# busfahrer_pi.net
KiCad netlist of a schematic drawn in EAGLE
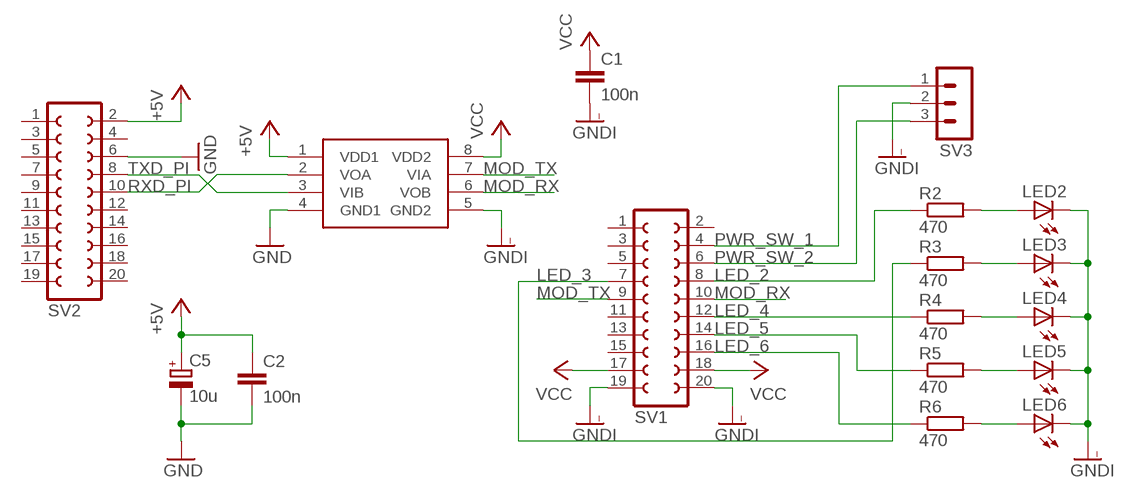
[diagram p0: schematic, sheet 1]

(export (version "E")
  (design (tool "Eeschema 10.0.6"))
  (components
    (comp (ref "C1")
      (value "100n")
      (footprint "eagle-import:C0805")
      (libsource (lib "eagle-import") (part "C-EUC0805"))
    )
    (comp (ref "C2")
      (value "100n")
      (footprint "eagle-import:C0805")
      (libsource (lib "eagle-import") (part "C-EUC0805"))
    )
    (comp (ref "C5")
      (value "10u")
      (footprint "eagle-import:E1,8-4")
      (libsource (lib "eagle-import") (part "CPOL-EUE1.8-4"))
    )
    (comp (ref "LED2")
      (value "LEDCHIPLED_0805")
      (footprint "eagle-import:CHIPLED_0805")
      (libsource (lib "eagle-import") (part "LEDCHIPLED_0805"))
    )
    (comp (ref "LED3")
      (value "LEDCHIPLED_0805")
      (footprint "eagle-import:CHIPLED_0805")
      (libsource (lib "eagle-import") (part "LEDCHIPLED_0805"))
    )
    (comp (ref "LED4")
      (value "LEDCHIPLED_0805")
      (footprint "eagle-import:CHIPLED_0805")
      (libsource (lib "eagle-import") (part "LEDCHIPLED_0805"))
    )
    (comp (ref "LED5")
      (value "LEDCHIPLED_0805")
      (footprint "eagle-import:CHIPLED_0805")
      (libsource (lib "eagle-import") (part "LEDCHIPLED_0805"))
    )
    (comp (ref "LED6")
      (value "LEDCHIPLED_0805")
      (footprint "eagle-import:CHIPLED_0805")
      (libsource (lib "eagle-import") (part "LEDCHIPLED_0805"))
    )
    (comp (ref "R2")
      (value "470")
      (footprint "eagle-import:R0805")
      (libsource (lib "eagle-import") (part "R-EU_R0805"))
    )
    (comp (ref "R3")
      (value "470")
      (footprint "eagle-import:R0805")
      (libsource (lib "eagle-import") (part "R-EU_R0805"))
    )
    (comp (ref "R4")
      (value "470")
      (footprint "eagle-import:R0805")
      (libsource (lib "eagle-import") (part "R-EU_R0805"))
    )
    (comp (ref "R5")
      (value "470")
      (footprint "eagle-import:R0805")
      (libsource (lib "eagle-import") (part "R-EU_R0805"))
    )
    (comp (ref "R6")
      (value "470")
      (footprint "eagle-import:R0805")
      (libsource (lib "eagle-import") (part "R-EU_R0805"))
    )
    (comp (ref "SV1")
      (value "FE10-2")
      (footprint "eagle-import:FE10-2")
      (libsource (lib "eagle-import") (part "FE10-2"))
    )
    (comp (ref "SV2")
      (value "FE10-2")
      (footprint "eagle-import:FE10-2")
      (fields (field (name "OC_FARNELL") "unknown") (field (name "OC_NEWARK") "unknown"))
      (libsource (lib "eagle-import") (part "FE10-2"))
    )
    (comp (ref "SV3")
      (value "MA03-1")
      (footprint "eagle-import:MA03-1")
      (libsource (lib "eagle-import") (part "MA03-1"))
    )
    (comp (ref "U$1")
      (value "ADUM3211")
      (footprint "eagle-import:SO8")
      (libsource (lib "eagle-import") (part "ADUM3211"))
    )
  )
  (nets
    (net (code "1") (name "+5V") (class "Default")
      (node (ref "C2") (pin "1") (pinfunction "1_1") (pintype "passive"))
      (node (ref "C5") (pin "+") (pinfunction "+_+") (pintype "passive"))
      (node (ref "SV2") (pin "2") (pinfunction "2_2") (pintype "passive"))
      (node (ref "U$1") (pin "1") (pinfunction "VDD1_1") (pintype "bidirectional"))
    )
    (net (code "2") (name "/LED_2") (class "Default")
      (node (ref "R2") (pin "1") (pinfunction "1_1") (pintype "passive"))
      (node (ref "SV1") (pin "8") (pinfunction "8_8") (pintype "passive"))
    )
    (net (code "3") (name "/LED_3") (class "Default")
      (node (ref "R3") (pin "1") (pinfunction "1_1") (pintype "passive"))
      (node (ref "SV1") (pin "7") (pinfunction "7_7") (pintype "passive"))
    )
    (net (code "4") (name "/LED_4") (class "Default")
      (node (ref "R4") (pin "1") (pinfunction "1_1") (pintype "passive"))
      (node (ref "SV1") (pin "12") (pinfunction "12_12") (pintype "passive"))
    )
    (net (code "5") (name "/LED_5") (class "Default")
      (node (ref "R5") (pin "1") (pinfunction "1_1") (pintype "passive"))
      (node (ref "SV1") (pin "14") (pinfunction "14_14") (pintype "passive"))
    )
    (net (code "6") (name "/LED_6") (class "Default")
      (node (ref "R6") (pin "1") (pinfunction "1_1") (pintype "passive"))
      (node (ref "SV1") (pin "16") (pinfunction "16_16") (pintype "passive"))
    )
    (net (code "7") (name "/MOD_RX") (class "Default")
      (node (ref "SV1") (pin "10") (pinfunction "10_10") (pintype "passive"))
      (node (ref "U$1") (pin "6") (pinfunction "VOB_6") (pintype "bidirectional"))
    )
    (net (code "8") (name "/MOD_TX") (class "Default")
      (node (ref "SV1") (pin "9") (pinfunction "9_9") (pintype "passive"))
      (node (ref "U$1") (pin "7") (pinfunction "VIA_7") (pintype "bidirectional"))
    )
    (net (code "9") (name "/PWR_SW_1") (class "Default")
      (node (ref "SV1") (pin "4") (pinfunction "4_4") (pintype "passive"))
      (node (ref "SV3") (pin "1") (pinfunction "1_1") (pintype "passive"))
    )
    (net (code "10") (name "/PWR_SW_2") (class "Default")
      (node (ref "SV1") (pin "6") (pinfunction "6_6") (pintype "passive"))
      (node (ref "SV3") (pin "3") (pinfunction "3_3") (pintype "passive"))
    )
    (net (code "11") (name "/RXD_PI") (class "Default")
      (node (ref "SV2") (pin "10") (pinfunction "10_10") (pintype "passive"))
      (node (ref "U$1") (pin "2") (pinfunction "VOA_2") (pintype "bidirectional"))
    )
    (net (code "12") (name "/TXD_PI") (class "Default")
      (node (ref "SV2") (pin "8") (pinfunction "8_8") (pintype "passive"))
      (node (ref "U$1") (pin "3") (pinfunction "VIB_3") (pintype "bidirectional"))
    )
    (net (code "13") (name "GND") (class "Default")
      (node (ref "C2") (pin "2") (pinfunction "2_2") (pintype "passive"))
      (node (ref "C5") (pin "-") (pinfunction "-_-") (pintype "passive"))
      (node (ref "SV2") (pin "6") (pinfunction "6_6") (pintype "passive"))
      (node (ref "U$1") (pin "4") (pinfunction "GND1_4") (pintype "bidirectional"))
    )
    (net (code "14") (name "GNDI") (class "Default")
      (node (ref "C1") (pin "2") (pinfunction "2_2") (pintype "passive"))
      (node (ref "LED2") (pin "C") (pinfunction "C_C") (pintype "passive"))
      (node (ref "LED3") (pin "C") (pinfunction "C_C") (pintype "passive"))
      (node (ref "LED4") (pin "C") (pinfunction "C_C") (pintype "passive"))
      (node (ref "LED5") (pin "C") (pinfunction "C_C") (pintype "passive"))
      (node (ref "LED6") (pin "C") (pinfunction "C_C") (pintype "passive"))
      (node (ref "SV1") (pin "19") (pinfunction "19_19") (pintype "passive"))
      (node (ref "SV1") (pin "20") (pinfunction "20_20") (pintype "passive"))
      (node (ref "SV3") (pin "2") (pinfunction "2_2") (pintype "passive"))
      (node (ref "U$1") (pin "5") (pinfunction "GND2_5") (pintype "bidirectional"))
    )
    (net (code "15") (name "Net-(LED2-PadA)") (class "Default")
      (node (ref "LED2") (pin "A") (pinfunction "A_A") (pintype "passive"))
      (node (ref "R2") (pin "2") (pinfunction "2_2") (pintype "passive"))
    )
    (net (code "16") (name "Net-(LED3-PadA)") (class "Default")
      (node (ref "LED3") (pin "A") (pinfunction "A_A") (pintype "passive"))
      (node (ref "R3") (pin "2") (pinfunction "2_2") (pintype "passive"))
    )
    (net (code "17") (name "Net-(LED4-PadA)") (class "Default")
      (node (ref "LED4") (pin "A") (pinfunction "A_A") (pintype "passive"))
      (node (ref "R4") (pin "2") (pinfunction "2_2") (pintype "passive"))
    )
    (net (code "18") (name "Net-(LED5-PadA)") (class "Default")
      (node (ref "LED5") (pin "A") (pinfunction "A_A") (pintype "passive"))
      (node (ref "R5") (pin "2") (pinfunction "2_2") (pintype "passive"))
    )
    (net (code "19") (name "Net-(LED6-PadA)") (class "Default")
      (node (ref "LED6") (pin "A") (pinfunction "A_A") (pintype "passive"))
      (node (ref "R6") (pin "2") (pinfunction "2_2") (pintype "passive"))
    )
    (net (code "20") (name "VCC") (class "Default")
      (node (ref "C1") (pin "1") (pinfunction "1_1") (pintype "passive"))
      (node (ref "SV1") (pin "17") (pinfunction "17_17") (pintype "passive"))
      (node (ref "SV1") (pin "18") (pinfunction "18_18") (pintype "passive"))
      (node (ref "U$1") (pin "8") (pinfunction "VDD2_8") (pintype "bidirectional"))
    )
    (net (code "21") (name "unconnected-(SV1-Pad1)") (class "Default")
      (node (ref "SV1") (pin "1") (pinfunction "1_1") (pintype "passive"))
    )
    (net (code "22") (name "unconnected-(SV1-Pad2)") (class "Default")
      (node (ref "SV1") (pin "2") (pinfunction "2_2") (pintype "passive"))
    )
    (net (code "23") (name "unconnected-(SV1-Pad3)") (class "Default")
      (node (ref "SV1") (pin "3") (pinfunction "3_3") (pintype "passive"))
    )
    (net (code "24") (name "unconnected-(SV1-Pad5)") (class "Default")
      (node (ref "SV1") (pin "5") (pinfunction "5_5") (pintype "passive"))
    )
    (net (code "25") (name "unconnected-(SV1-Pad11)") (class "Default")
      (node (ref "SV1") (pin "11") (pinfunction "11_11") (pintype "passive"))
    )
    (net (code "26") (name "unconnected-(SV1-Pad13)") (class "Default")
      (node (ref "SV1") (pin "13") (pinfunction "13_13") (pintype "passive"))
    )
    (net (code "27") (name "unconnected-(SV1-Pad15)") (class "Default")
      (node (ref "SV1") (pin "15") (pinfunction "15_15") (pintype "passive"))
    )
    (net (code "28") (name "unconnected-(SV2-Pad1)") (class "Default")
      (node (ref "SV2") (pin "1") (pinfunction "1_1") (pintype "passive"))
    )
    (net (code "29") (name "unconnected-(SV2-Pad3)") (class "Default")
      (node (ref "SV2") (pin "3") (pinfunction "3_3") (pintype "passive"))
    )
    (net (code "30") (name "unconnected-(SV2-Pad4)") (class "Default")
      (node (ref "SV2") (pin "4") (pinfunction "4_4") (pintype "passive"))
    )
    (net (code "31") (name "unconnected-(SV2-Pad5)") (class "Default")
      (node (ref "SV2") (pin "5") (pinfunction "5_5") (pintype "passive"))
    )
    (net (code "32") (name "unconnected-(SV2-Pad7)") (class "Default")
      (node (ref "SV2") (pin "7") (pinfunction "7_7") (pintype "passive"))
    )
    (net (code "33") (name "unconnected-(SV2-Pad9)") (class "Default")
      (node (ref "SV2") (pin "9") (pinfunction "9_9") (pintype "passive"))
    )
    (net (code "34") (name "unconnected-(SV2-Pad11)") (class "Default")
      (node (ref "SV2") (pin "11") (pinfunction "11_11") (pintype "passive"))
    )
    (net (code "35") (name "unconnected-(SV2-Pad12)") (class "Default")
      (node (ref "SV2") (pin "12") (pinfunction "12_12") (pintype "passive"))
    )
    (net (code "36") (name "unconnected-(SV2-Pad13)") (class "Default")
      (node (ref "SV2") (pin "13") (pinfunction "13_13") (pintype "passive"))
    )
    (net (code "37") (name "unconnected-(SV2-Pad14)") (class "Default")
      (node (ref "SV2") (pin "14") (pinfunction "14_14") (pintype "passive"))
    )
    (net (code "38") (name "unconnected-(SV2-Pad15)") (class "Default")
      (node (ref "SV2") (pin "15") (pinfunction "15_15") (pintype "passive"))
    )
    (net (code "39") (name "unconnected-(SV2-Pad16)") (class "Default")
      (node (ref "SV2") (pin "16") (pinfunction "16_16") (pintype "passive"))
    )
    (net (code "40") (name "unconnected-(SV2-Pad17)") (class "Default")
      (node (ref "SV2") (pin "17") (pinfunction "17_17") (pintype "passive"))
    )
    (net (code "41") (name "unconnected-(SV2-Pad18)") (class "Default")
      (node (ref "SV2") (pin "18") (pinfunction "18_18") (pintype "passive"))
    )
    (net (code "42") (name "unconnected-(SV2-Pad19)") (class "Default")
      (node (ref "SV2") (pin "19") (pinfunction "19_19") (pintype "passive"))
    )
    (net (code "43") (name "unconnected-(SV2-Pad20)") (class "Default")
      (node (ref "SV2") (pin "20") (pinfunction "20_20") (pintype "passive"))
    )
  )
)
